# TakpadV6_1.net
KiCad netlist of a schematic drawn in EAGLE
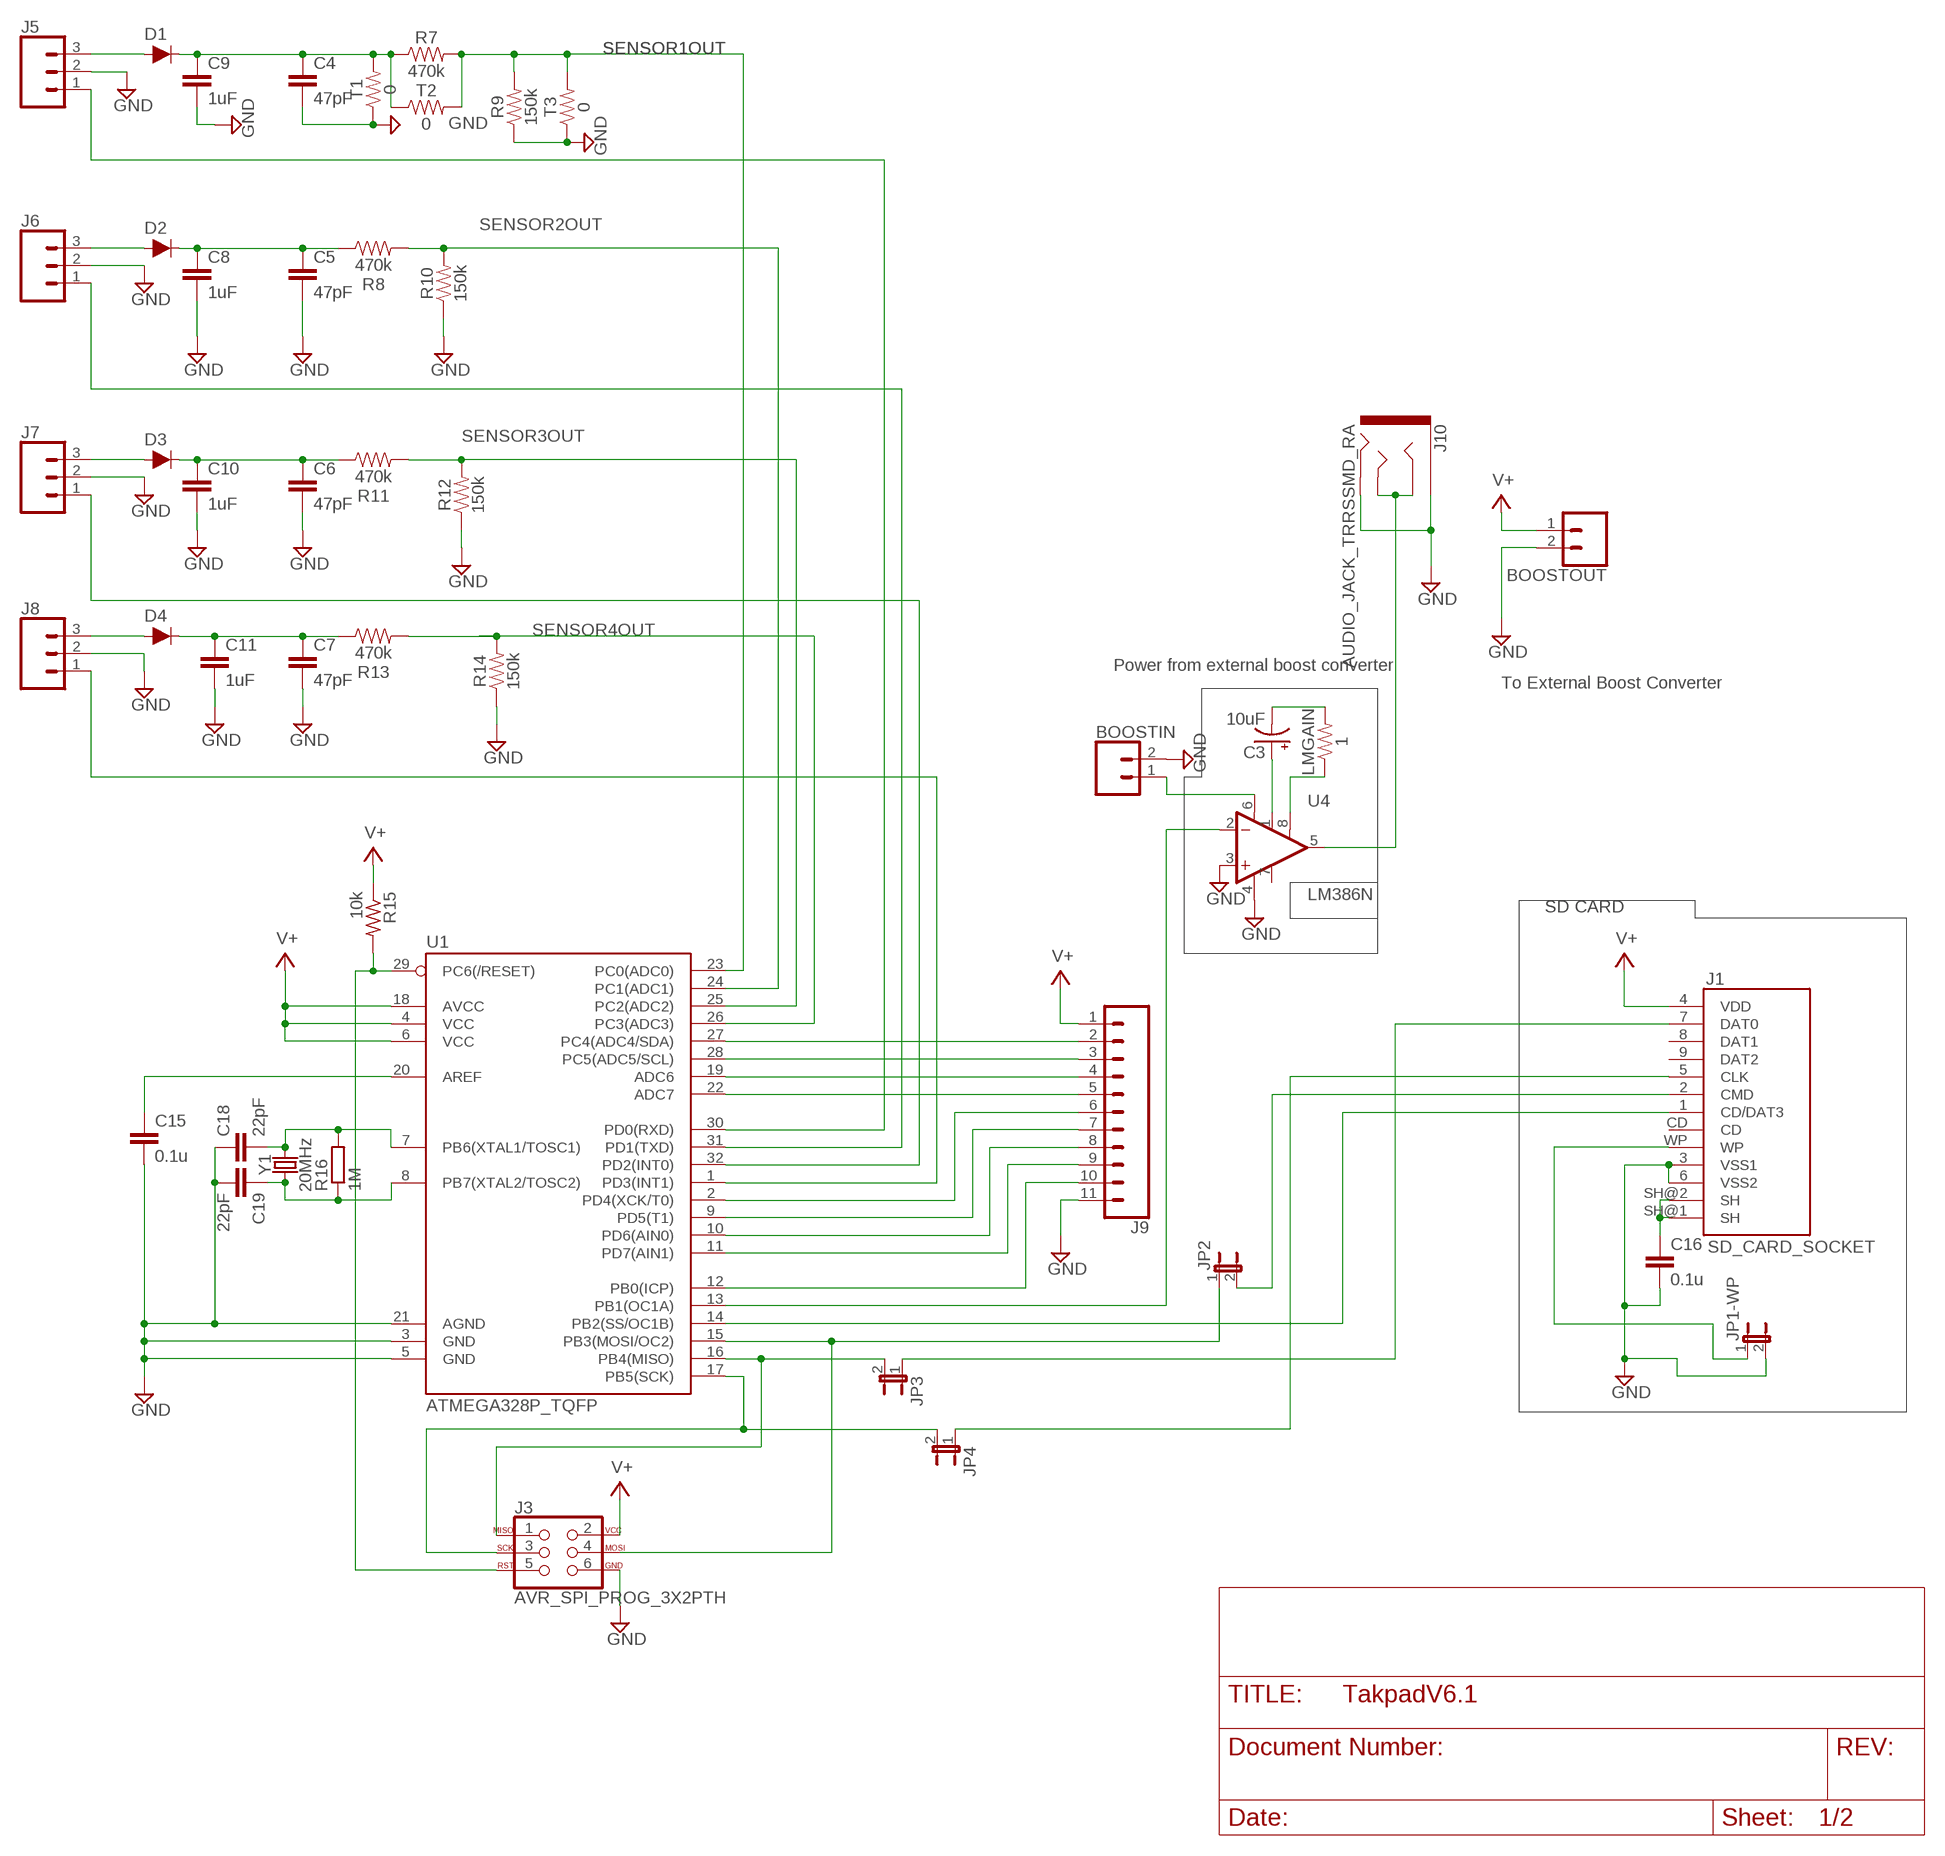
[diagram p0: schematic, sheet 1]
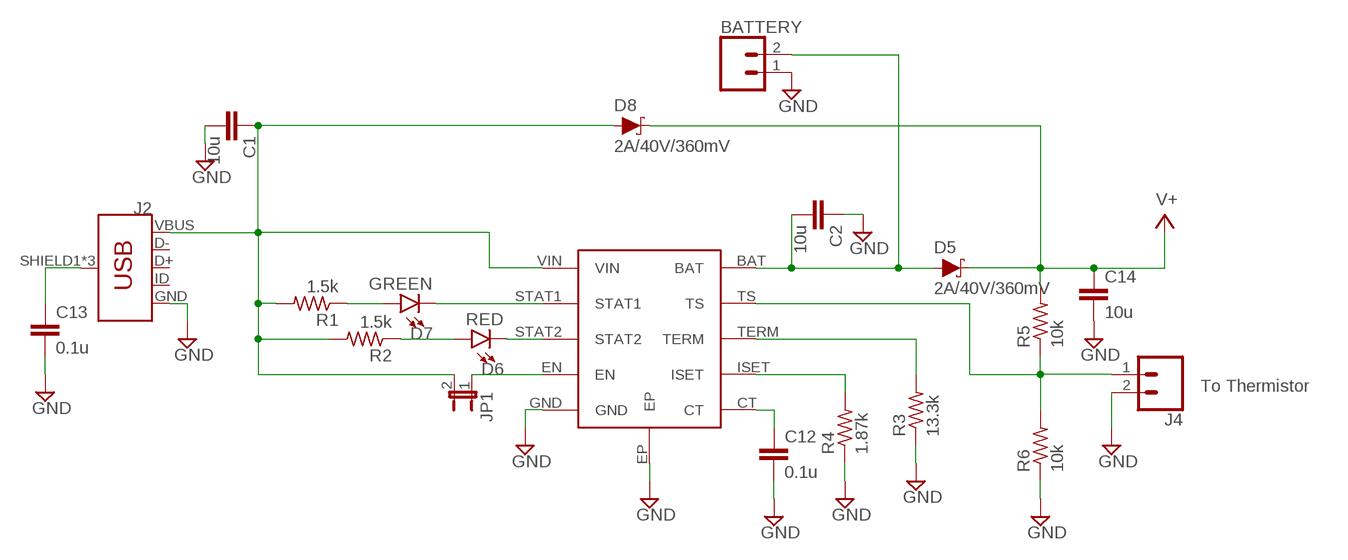
[diagram p1: schematic, sheet 2]

(export (version "E")
  (design (tool "Eeschema 10.0.6"))
  (components
    (comp (ref "BOOSTIN")
      (value "CONN_02")
      (footprint "eagle-import:1X02")
      (libsource (lib "eagle-import") (part "CONN_02"))
    )
    (comp (ref "BOOSTOUT")
      (value "CONN_02")
      (footprint "eagle-import:1X02")
      (libsource (lib "eagle-import") (part "CONN_02"))
    )
    (comp (ref "C3")
      (value "10uF")
      (footprint "eagle-import:CPOL-RADIAL-2.5MM-5MM-KIT")
      (libsource (lib "eagle-import") (part "10UF-POLAR-RADIAL-2.5MM-KIT-25V-20%"))
    )
    (comp (ref "C4")
      (value "47pF")
      (footprint "eagle-import:0603")
      (libsource (lib "eagle-import") (part "47PF-0603-50V-5%"))
    )
    (comp (ref "C5")
      (value "47pF")
      (footprint "eagle-import:0603")
      (libsource (lib "eagle-import") (part "47PF-0603-50V-5%"))
    )
    (comp (ref "C6")
      (value "47pF")
      (footprint "eagle-import:0603")
      (libsource (lib "eagle-import") (part "47PF-0603-50V-5%"))
    )
    (comp (ref "C7")
      (value "47pF")
      (footprint "eagle-import:0603")
      (libsource (lib "eagle-import") (part "47PF-0603-50V-5%"))
    )
    (comp (ref "C8")
      (value "1uF")
      (footprint "eagle-import:0603")
      (libsource (lib "eagle-import") (part "47PF-0603-50V-5%"))
    )
    (comp (ref "C9")
      (value "1uF")
      (footprint "eagle-import:0603")
      (libsource (lib "eagle-import") (part "47PF-0603-50V-5%"))
    )
    (comp (ref "C10")
      (value "1uF")
      (footprint "eagle-import:0603")
      (libsource (lib "eagle-import") (part "47PF-0603-50V-5%"))
    )
    (comp (ref "C11")
      (value "1uF")
      (footprint "eagle-import:0603")
      (libsource (lib "eagle-import") (part "47PF-0603-50V-5%"))
    )
    (comp (ref "C15")
      (value "0.1u")
      (footprint "eagle-import:C0402")
      (libsource (lib "eagle-import") (part "C-EUC0402"))
    )
    (comp (ref "C16")
      (value "0.1u")
      (footprint "eagle-import:C0402")
      (libsource (lib "eagle-import") (part "C-EUC0402"))
    )
    (comp (ref "C18")
      (value "22pF")
      (footprint "eagle-import:C0402")
      (libsource (lib "eagle-import") (part "resistor_348_C-EUC0402"))
    )
    (comp (ref "C19")
      (value "22pF")
      (footprint "eagle-import:C0402")
      (libsource (lib "eagle-import") (part "resistor_348_C-EUC0402"))
    )
    (comp (ref "D1")
      (value "200mA/100V/1V")
      (footprint "eagle-import:DIODE-1N4148")
      (libsource (lib "eagle-import") (part "DIODE-1N4148"))
    )
    (comp (ref "D2")
      (value "200mA/100V/1V")
      (footprint "eagle-import:DIODE-1N4148")
      (libsource (lib "eagle-import") (part "DIODE-1N4148"))
    )
    (comp (ref "D3")
      (value "200mA/100V/1V")
      (footprint "eagle-import:DIODE-1N4148")
      (libsource (lib "eagle-import") (part "DIODE-1N4148"))
    )
    (comp (ref "D4")
      (value "200mA/100V/1V")
      (footprint "eagle-import:DIODE-1N4148")
      (libsource (lib "eagle-import") (part "DIODE-1N4148"))
    )
    (comp (ref "J1")
      (value "SD_CARD_SOCKET")
      (footprint "eagle-import:SD")
      (libsource (lib "eagle-import") (part "SD_CARD_SOCKET"))
    )
    (comp (ref "J3")
      (value "AVR_SPI_PROG_3X2PTH")
      (footprint "eagle-import:2X3")
      (libsource (lib "eagle-import") (part "AVR_SPI_PROG_3X2PTH"))
    )
    (comp (ref "J5")
      (value "CONN_03")
      (footprint "eagle-import:1X03")
      (libsource (lib "eagle-import") (part "CONN_03"))
    )
    (comp (ref "J6")
      (value "CONN_03")
      (footprint "eagle-import:1X03")
      (libsource (lib "eagle-import") (part "CONN_03"))
    )
    (comp (ref "J7")
      (value "CONN_03")
      (footprint "eagle-import:1X03")
      (libsource (lib "eagle-import") (part "CONN_03"))
    )
    (comp (ref "J8")
      (value "CONN_03")
      (footprint "eagle-import:1X03")
      (libsource (lib "eagle-import") (part "CONN_03"))
    )
    (comp (ref "J9")
      (value "CONN_11")
      (footprint "eagle-import:1X11")
      (libsource (lib "eagle-import") (part "CONN_11"))
    )
    (comp (ref "J10")
      (value "AUDIO_JACK_TRRSSMD_RA")
      (footprint "eagle-import:AUDIO_JACK_3.5MM_TRRS_SMD_RA")
      (libsource (lib "eagle-import") (part "AUDIO_JACK_TRRSSMD_RA"))
    )
    (comp (ref "JP1-WP")
      (value "JUMPER-2PTH")
      (footprint "eagle-import:1X02")
      (libsource (lib "eagle-import") (part "JUMPER-2PTH"))
    )
    (comp (ref "JP2")
      (value "JUMPER-2PTH")
      (footprint "eagle-import:1X02")
      (libsource (lib "eagle-import") (part "JUMPER-2PTH"))
    )
    (comp (ref "JP3")
      (value "JUMPER-2PTH")
      (footprint "eagle-import:1X02")
      (libsource (lib "eagle-import") (part "JUMPER-2PTH"))
    )
    (comp (ref "JP4")
      (value "JUMPER-2PTH")
      (footprint "eagle-import:1X02")
      (libsource (lib "eagle-import") (part "JUMPER-2PTH"))
    )
    (comp (ref "LMGAIN")
      (value "1")
      (footprint "eagle-import:0603")
      (libsource (lib "eagle-import") (part "1OHM-0603-1/10W-1%"))
    )
    (comp (ref "R7")
      (value "470k")
      (footprint "eagle-import:AXIAL-0.3")
      (libsource (lib "eagle-import") (part "1KOHM-HORIZ-1/4W-1%"))
    )
    (comp (ref "R8")
      (value "470k")
      (footprint "eagle-import:AXIAL-0.3")
      (libsource (lib "eagle-import") (part "1KOHM-HORIZ-1/4W-1%"))
    )
    (comp (ref "R9")
      (value "150k")
      (footprint "eagle-import:AXIAL-0.3")
      (libsource (lib "eagle-import") (part "1KOHM-HORIZ-1/4W-1%"))
    )
    (comp (ref "R10")
      (value "150k")
      (footprint "eagle-import:AXIAL-0.3")
      (libsource (lib "eagle-import") (part "1KOHM-HORIZ-1/4W-1%"))
    )
    (comp (ref "R11")
      (value "470k")
      (footprint "eagle-import:AXIAL-0.3")
      (libsource (lib "eagle-import") (part "1KOHM-HORIZ-1/4W-1%"))
    )
    (comp (ref "R12")
      (value "150k")
      (footprint "eagle-import:AXIAL-0.3")
      (libsource (lib "eagle-import") (part "1KOHM-HORIZ-1/4W-1%"))
    )
    (comp (ref "R13")
      (value "470k")
      (footprint "eagle-import:AXIAL-0.3")
      (libsource (lib "eagle-import") (part "1KOHM-HORIZ-1/4W-1%"))
    )
    (comp (ref "R14")
      (value "150k")
      (footprint "eagle-import:AXIAL-0.3")
      (libsource (lib "eagle-import") (part "1KOHM-HORIZ-1/4W-1%"))
    )
    (comp (ref "R15")
      (value "10k")
      (footprint "eagle-import:M1206")
      (libsource (lib "eagle-import") (part "R-US_M1206"))
    )
    (comp (ref "R16")
      (value "1M")
      (footprint "eagle-import:R0402")
      (libsource (lib "eagle-import") (part "R-EU_R0402"))
    )
    (comp (ref "T1")
      (value "0")
      (footprint "eagle-import:AXIAL-0.3")
      (libsource (lib "eagle-import") (part "1KOHM-HORIZ-1/4W-1%"))
    )
    (comp (ref "T2")
      (value "0")
      (footprint "eagle-import:AXIAL-0.3")
      (libsource (lib "eagle-import") (part "1KOHM-HORIZ-1/4W-1%"))
    )
    (comp (ref "T3")
      (value "0")
      (footprint "eagle-import:AXIAL-0.3")
      (libsource (lib "eagle-import") (part "1KOHM-HORIZ-1/4W-1%"))
    )
    (comp (ref "U1")
      (value "ATMEGA328P_TQFP")
      (footprint "eagle-import:TQFP32-08")
      (libsource (lib "eagle-import") (part "ATMEGA328P_TQFP"))
    )
    (comp (ref "U4")
      (value "LM386N")
      (footprint "eagle-import:DIP08")
      (libsource (lib "eagle-import") (part "LM386"))
    )
    (comp (ref "Y1")
      (value "20MHz")
      (footprint "eagle-import:HC49US")
      (libsource (lib "eagle-import") (part "CRYSTAL-16MHZPTH-HC49US"))
    )
    (comp (ref "BATTERY")
      (value "CONN_02")
      (footprint "eagle-import:1X02")
      (libsource (lib "eagle-import") (part "CONN_02"))
    )
    (comp (ref "C1")
      (value "10u")
      (footprint "eagle-import:C0402")
      (libsource (lib "eagle-import") (part "C-EUC0402"))
    )
    (comp (ref "C2")
      (value "10u")
      (footprint "eagle-import:C0402")
      (libsource (lib "eagle-import") (part "C-EUC0402"))
    )
    (comp (ref "C12")
      (value "0.1u")
      (footprint "eagle-import:C0402")
      (libsource (lib "eagle-import") (part "C-EUC0402"))
    )
    (comp (ref "C13")
      (value "0.1u")
      (footprint "eagle-import:C0402")
      (libsource (lib "eagle-import") (part "C-EUC0402"))
    )
    (comp (ref "C14")
      (value "10u")
      (footprint "eagle-import:C0402")
      (libsource (lib "eagle-import") (part "C-EUC0402"))
    )
    (comp (ref "D5")
      (value "2A/40V/360mV")
      (footprint "eagle-import:SMA-DIODE")
      (libsource (lib "eagle-import") (part "DIODE-SCHOTTKY-B340A"))
    )
    (comp (ref "D6")
      (value "RED")
      (footprint "eagle-import:LED-1206")
      (libsource (lib "eagle-import") (part "LED-RED1206"))
    )
    (comp (ref "D7")
      (value "GREEN")
      (footprint "eagle-import:LED-1206")
      (libsource (lib "eagle-import") (part "LED-GREEN1206"))
    )
    (comp (ref "D8")
      (value "2A/40V/360mV")
      (footprint "eagle-import:SMA-DIODE")
      (libsource (lib "eagle-import") (part "DIODE-SCHOTTKY-B340A"))
    )
    (comp (ref "J2")
      (value "USB_MICRO-BREDUCED_PASTE")
      (footprint "eagle-import:USB-B-MICRO-SMD_RED_PASTE")
      (libsource (lib "eagle-import") (part "USB_MICRO-BREDUCED_PASTE"))
    )
    (comp (ref "J4")
      (value "CONN_02")
      (footprint "eagle-import:1X02")
      (libsource (lib "eagle-import") (part "CONN_02"))
    )
    (comp (ref "JP1")
      (value "JUMPER-2PTH")
      (footprint "eagle-import:1X02")
      (libsource (lib "eagle-import") (part "JUMPER-2PTH"))
    )
    (comp (ref "R1")
      (value "1.5k")
      (footprint "eagle-import:M1206")
      (libsource (lib "eagle-import") (part "R-US_M1206"))
    )
    (comp (ref "R2")
      (value "1.5k")
      (footprint "eagle-import:M1206")
      (libsource (lib "eagle-import") (part "R-US_M1206"))
    )
    (comp (ref "R3")
      (value "13.3k")
      (footprint "eagle-import:M1206")
      (libsource (lib "eagle-import") (part "R-US_M1206"))
    )
    (comp (ref "R4")
      (value "1.87k")
      (footprint "eagle-import:M1206")
      (libsource (lib "eagle-import") (part "R-US_M1206"))
    )
    (comp (ref "R5")
      (value "10k")
      (footprint "eagle-import:M1206")
      (libsource (lib "eagle-import") (part "R-US_M1206"))
    )
    (comp (ref "R6")
      (value "10k")
      (footprint "eagle-import:M1206")
      (libsource (lib "eagle-import") (part "R-US_M1206"))
    )
    (comp (ref "U$1")
      (value "AAT3693")
      (footprint "eagle-import:IDH-AA-T1")
      (libsource (lib "eagle-import") (part "AAT3693"))
    )
  )
  (nets
    (net (code "1") (name "GND") (class "Default")
      (node (ref "BATTERY") (pin "1") (pinfunction "1_1") (pintype "passive"))
      (node (ref "BOOSTIN") (pin "2") (pinfunction "2_2") (pintype "passive"))
      (node (ref "BOOSTOUT") (pin "2") (pinfunction "2_2") (pintype "passive"))
      (node (ref "C1") (pin "2") (pinfunction "2_2") (pintype "passive"))
      (node (ref "C10") (pin "2") (pinfunction "2_2") (pintype "passive"))
      (node (ref "C11") (pin "2") (pinfunction "2_2") (pintype "passive"))
      (node (ref "C12") (pin "2") (pinfunction "2_2") (pintype "passive"))
      (node (ref "C13") (pin "2") (pinfunction "2_2") (pintype "passive"))
      (node (ref "C14") (pin "2") (pinfunction "2_2") (pintype "passive"))
      (node (ref "C15") (pin "2") (pinfunction "2_2") (pintype "passive"))
      (node (ref "C16") (pin "2") (pinfunction "2_2") (pintype "passive"))
      (node (ref "C18") (pin "1") (pinfunction "1_1") (pintype "passive"))
      (node (ref "C19") (pin "2") (pinfunction "2_2") (pintype "passive"))
      (node (ref "C2") (pin "1") (pinfunction "1_1") (pintype "passive"))
      (node (ref "C4") (pin "2") (pinfunction "2_2") (pintype "passive"))
      (node (ref "C5") (pin "2") (pinfunction "2_2") (pintype "passive"))
      (node (ref "C6") (pin "2") (pinfunction "2_2") (pintype "passive"))
      (node (ref "C7") (pin "2") (pinfunction "2_2") (pintype "passive"))
      (node (ref "C8") (pin "2") (pinfunction "2_2") (pintype "passive"))
      (node (ref "C9") (pin "2") (pinfunction "2_2") (pintype "passive"))
      (node (ref "J1") (pin "3") (pinfunction "VSS1_3") (pintype "power_in"))
      (node (ref "J1") (pin "6") (pinfunction "VSS2_6") (pintype "power_in"))
      (node (ref "J10") (pin "EARTH") (pinfunction "EARTH_EARTH") (pintype "bidirectional"))
      (node (ref "J10") (pin "RING2") (pinfunction "RING2_RING2") (pintype "bidirectional"))
      (node (ref "J2") (pin "GND") (pinfunction "GND_GND") (pintype "power_in"))
      (node (ref "J3") (pin "6") (pinfunction "6_6") (pintype "passive"))
      (node (ref "J4") (pin "2") (pinfunction "2_2") (pintype "passive"))
      (node (ref "J5") (pin "2") (pinfunction "2_2") (pintype "passive"))
      (node (ref "J6") (pin "2") (pinfunction "2_2") (pintype "passive"))
      (node (ref "J7") (pin "2") (pinfunction "2_2") (pintype "passive"))
      (node (ref "J8") (pin "2") (pinfunction "2_2") (pintype "passive"))
      (node (ref "J9") (pin "11") (pinfunction "11_11") (pintype "passive"))
      (node (ref "JP1-WP") (pin "2") (pinfunction "2_2") (pintype "passive"))
      (node (ref "R10") (pin "P$1") (pinfunction "1_P$1") (pintype "passive"))
      (node (ref "R12") (pin "P$1") (pinfunction "1_P$1") (pintype "passive"))
      (node (ref "R14") (pin "P$1") (pinfunction "1_P$1") (pintype "passive"))
      (node (ref "R3") (pin "1") (pinfunction "1_1") (pintype "passive"))
      (node (ref "R4") (pin "1") (pinfunction "1_1") (pintype "passive"))
      (node (ref "R6") (pin "1") (pinfunction "1_1") (pintype "passive"))
      (node (ref "R9") (pin "P$1") (pinfunction "1_P$1") (pintype "passive"))
      (node (ref "T1") (pin "P$1") (pinfunction "1_P$1") (pintype "passive"))
      (node (ref "T3") (pin "P$1") (pinfunction "1_P$1") (pintype "passive"))
      (node (ref "U$1") (pin "EP") (pinfunction "EP_EP") (pintype "bidirectional"))
      (node (ref "U$1") (pin "GND") (pinfunction "GND_GND") (pintype "bidirectional"))
      (node (ref "U1") (pin "21") (pinfunction "AGND_21") (pintype "bidirectional"))
      (node (ref "U1") (pin "3") (pinfunction "GND_3") (pintype "bidirectional"))
      (node (ref "U1") (pin "5") (pinfunction "GND_5") (pintype "bidirectional"))
      (node (ref "U4") (pin "3") (pinfunction "+IN_3") (pintype "input"))
      (node (ref "U4") (pin "4") (pinfunction "V-_4") (pintype "power_in"))
    )
    (net (code "2") (name "Net-(BATTERY-Pad2)") (class "Default")
      (node (ref "BATTERY") (pin "2") (pinfunction "2_2") (pintype "passive"))
      (node (ref "C2") (pin "2") (pinfunction "2_2") (pintype "passive"))
      (node (ref "D5") (pin "A") (pinfunction "A_A") (pintype "passive"))
      (node (ref "U$1") (pin "BAT") (pinfunction "BAT_BAT") (pintype "bidirectional"))
    )
    (net (code "3") (name "Net-(C1-Pad1)") (class "Default")
      (node (ref "C1") (pin "1") (pinfunction "1_1") (pintype "passive"))
      (node (ref "D8") (pin "A") (pinfunction "A_A") (pintype "passive"))
      (node (ref "J2") (pin "VBUS") (pinfunction "VBUS_VBUS") (pintype "power_in"))
      (node (ref "JP1") (pin "2") (pinfunction "2_2") (pintype "passive"))
      (node (ref "R1") (pin "2") (pinfunction "2_2") (pintype "passive"))
      (node (ref "R2") (pin "2") (pinfunction "2_2") (pintype "passive"))
      (node (ref "U$1") (pin "VIN") (pinfunction "VIN_VIN") (pintype "bidirectional"))
    )
    (net (code "4") (name "Net-(C3-+)") (class "Default")
      (node (ref "C3") (pin "1") (pinfunction "+_1") (pintype "passive"))
      (node (ref "U4") (pin "1") (pinfunction "GAIN_1") (pintype "bidirectional"))
    )
    (net (code "5") (name "Net-(C3--)") (class "Default")
      (node (ref "C3") (pin "2") (pinfunction "-_2") (pintype "passive"))
      (node (ref "LMGAIN") (pin "2") (pinfunction "2_2") (pintype "passive"))
    )
    (net (code "6") (name "Net-(C12-Pad1)") (class "Default")
      (node (ref "C12") (pin "1") (pinfunction "1_1") (pintype "passive"))
      (node (ref "U$1") (pin "CT") (pinfunction "CT_CT") (pintype "bidirectional"))
    )
    (net (code "7") (name "Net-(C13-Pad1)") (class "Default")
      (node (ref "C13") (pin "1") (pinfunction "1_1") (pintype "passive"))
      (node (ref "J2") (pin "SHIELD1") (pinfunction "SHIELD_SHIELD1") (pintype "bidirectional"))
      (node (ref "J2") (pin "SHIELD2") (pinfunction "SHIELD_SHIELD2") (pintype "bidirectional"))
      (node (ref "J2") (pin "SHIELD3") (pinfunction "SHIELD_SHIELD3") (pintype "bidirectional"))
    )
    (net (code "8") (name "Net-(C16-Pad1)") (class "Default")
      (node (ref "C16") (pin "1") (pinfunction "1_1") (pintype "passive"))
      (node (ref "J1") (pin "SH@1") (pinfunction "SH_SH@1") (pintype "bidirectional"))
      (node (ref "J1") (pin "SH@2") (pinfunction "SH_SH@2") (pintype "bidirectional"))
    )
    (net (code "9") (name "Net-(D1-PadA)") (class "Default")
      (node (ref "D1") (pin "A") (pinfunction "A_A") (pintype "passive"))
      (node (ref "J5") (pin "3") (pinfunction "3_3") (pintype "passive"))
    )
    (net (code "10") (name "Net-(D2-PadA)") (class "Default")
      (node (ref "D2") (pin "A") (pinfunction "A_A") (pintype "passive"))
      (node (ref "J6") (pin "3") (pinfunction "3_3") (pintype "passive"))
    )
    (net (code "11") (name "Net-(D3-PadA)") (class "Default")
      (node (ref "D3") (pin "A") (pinfunction "A_A") (pintype "passive"))
      (node (ref "J7") (pin "3") (pinfunction "3_3") (pintype "passive"))
    )
    (net (code "12") (name "Net-(D4-PadA)") (class "Default")
      (node (ref "D4") (pin "A") (pinfunction "A_A") (pintype "passive"))
      (node (ref "J8") (pin "3") (pinfunction "3_3") (pintype "passive"))
    )
    (net (code "13") (name "Net-(D6-PadA)") (class "Default")
      (node (ref "D6") (pin "A") (pinfunction "A_A") (pintype "passive"))
      (node (ref "R2") (pin "1") (pinfunction "1_1") (pintype "passive"))
    )
    (net (code "14") (name "Net-(D6-PadC)") (class "Default")
      (node (ref "D6") (pin "C") (pinfunction "C_C") (pintype "passive"))
      (node (ref "U$1") (pin "STAT2") (pinfunction "STAT2_STAT2") (pintype "bidirectional"))
    )
    (net (code "15") (name "Net-(D7-PadA)") (class "Default")
      (node (ref "D7") (pin "A") (pinfunction "A_A") (pintype "passive"))
      (node (ref "R1") (pin "1") (pinfunction "1_1") (pintype "passive"))
    )
    (net (code "16") (name "Net-(D7-PadC)") (class "Default")
      (node (ref "D7") (pin "C") (pinfunction "C_C") (pintype "passive"))
      (node (ref "U$1") (pin "STAT1") (pinfunction "STAT1_STAT1") (pintype "bidirectional"))
    )
    (net (code "17") (name "Net-(J1-CD{slash}DAT3)") (class "Default")
      (node (ref "J1") (pin "1") (pinfunction "CD/DAT3_1") (pintype "bidirectional"))
      (node (ref "U1") (pin "14") (pinfunction "PB2(SS/OC1B)_14") (pintype "bidirectional"))
    )
    (net (code "18") (name "Net-(J1-CLK)") (class "Default")
      (node (ref "J1") (pin "5") (pinfunction "CLK_5") (pintype "bidirectional"))
      (node (ref "JP4") (pin "1") (pinfunction "1_1") (pintype "passive"))
    )
    (net (code "19") (name "Net-(J1-CMD)") (class "Default")
      (node (ref "J1") (pin "2") (pinfunction "CMD_2") (pintype "bidirectional"))
      (node (ref "JP2") (pin "2") (pinfunction "2_2") (pintype "passive"))
    )
    (net (code "20") (name "Net-(J1-DAT0)") (class "Default")
      (node (ref "J1") (pin "7") (pinfunction "DAT0_7") (pintype "bidirectional"))
      (node (ref "JP3") (pin "1") (pinfunction "1_1") (pintype "passive"))
    )
    (net (code "21") (name "Net-(J1-PadWP)") (class "Default")
      (node (ref "J1") (pin "WP") (pinfunction "WP_WP") (pintype "bidirectional"))
      (node (ref "JP1-WP") (pin "1") (pinfunction "1_1") (pintype "passive"))
    )
    (net (code "22") (name "Net-(J4-Pad1)") (class "Default")
      (node (ref "J4") (pin "1") (pinfunction "1_1") (pintype "passive"))
      (node (ref "R5") (pin "1") (pinfunction "1_1") (pintype "passive"))
      (node (ref "R6") (pin "2") (pinfunction "2_2") (pintype "passive"))
      (node (ref "U$1") (pin "TS") (pinfunction "TS_TS") (pintype "bidirectional"))
    )
    (net (code "23") (name "Net-(JP1-Pad1)") (class "Default")
      (node (ref "JP1") (pin "1") (pinfunction "1_1") (pintype "passive"))
      (node (ref "U$1") (pin "EN") (pinfunction "EN_EN") (pintype "bidirectional"))
    )
    (net (code "24") (name "Net-(LMGAIN-Pad1)") (class "Default")
      (node (ref "LMGAIN") (pin "1") (pinfunction "1_1") (pintype "passive"))
      (node (ref "U4") (pin "8") (pinfunction "GAIN_8") (pintype "bidirectional"))
    )
    (net (code "25") (name "Net-(R3-Pad2)") (class "Default")
      (node (ref "R3") (pin "2") (pinfunction "2_2") (pintype "passive"))
      (node (ref "U$1") (pin "TERM") (pinfunction "TERM_TERM") (pintype "bidirectional"))
    )
    (net (code "26") (name "Net-(R4-Pad2)") (class "Default")
      (node (ref "R4") (pin "2") (pinfunction "2_2") (pintype "passive"))
      (node (ref "U$1") (pin "ISET") (pinfunction "ISET_ISET") (pintype "bidirectional"))
    )
    (net (code "27") (name "Net-(R7-1)") (class "Default")
      (node (ref "C4") (pin "1") (pinfunction "1_1") (pintype "passive"))
      (node (ref "C9") (pin "1") (pinfunction "1_1") (pintype "passive"))
      (node (ref "D1") (pin "C") (pinfunction "C_C") (pintype "passive"))
      (node (ref "R7") (pin "P$1") (pinfunction "1_P$1") (pintype "passive"))
      (node (ref "T1") (pin "P$2") (pinfunction "2_P$2") (pintype "passive"))
      (node (ref "T2") (pin "P$1") (pinfunction "1_P$1") (pintype "passive"))
    )
    (net (code "28") (name "Net-(R8-1)") (class "Default")
      (node (ref "C5") (pin "1") (pinfunction "1_1") (pintype "passive"))
      (node (ref "C8") (pin "1") (pinfunction "1_1") (pintype "passive"))
      (node (ref "D2") (pin "C") (pinfunction "C_C") (pintype "passive"))
      (node (ref "R8") (pin "P$1") (pinfunction "1_P$1") (pintype "passive"))
    )
    (net (code "29") (name "Net-(R11-1)") (class "Default")
      (node (ref "C10") (pin "1") (pinfunction "1_1") (pintype "passive"))
      (node (ref "C6") (pin "1") (pinfunction "1_1") (pintype "passive"))
      (node (ref "D3") (pin "C") (pinfunction "C_C") (pintype "passive"))
      (node (ref "R11") (pin "P$1") (pinfunction "1_P$1") (pintype "passive"))
    )
    (net (code "30") (name "Net-(R13-1)") (class "Default")
      (node (ref "C11") (pin "1") (pinfunction "1_1") (pintype "passive"))
      (node (ref "C7") (pin "1") (pinfunction "1_1") (pintype "passive"))
      (node (ref "D4") (pin "C") (pinfunction "C_C") (pintype "passive"))
      (node (ref "R13") (pin "P$1") (pinfunction "1_P$1") (pintype "passive"))
    )
    (net (code "31") (name "Net-(U1-ADC6)") (class "Default")
      (node (ref "J9") (pin "4") (pinfunction "4_4") (pintype "passive"))
      (node (ref "U1") (pin "19") (pinfunction "ADC6_19") (pintype "bidirectional"))
    )
    (net (code "32") (name "Net-(U1-ADC7)") (class "Default")
      (node (ref "J9") (pin "5") (pinfunction "5_5") (pintype "passive"))
      (node (ref "U1") (pin "22") (pinfunction "ADC7_22") (pintype "bidirectional"))
    )
    (net (code "33") (name "Net-(U1-AREF)") (class "Default")
      (node (ref "C15") (pin "1") (pinfunction "1_1") (pintype "passive"))
      (node (ref "U1") (pin "20") (pinfunction "AREF_20") (pintype "bidirectional"))
    )
    (net (code "34") (name "Net-(U1-PB0(ICP))") (class "Default")
      (node (ref "J9") (pin "10") (pinfunction "10_10") (pintype "passive"))
      (node (ref "U1") (pin "12") (pinfunction "PB0(ICP)_12") (pintype "bidirectional"))
    )
    (net (code "35") (name "Net-(U1-PB1(OC1A))") (class "Default")
      (node (ref "U1") (pin "13") (pinfunction "PB1(OC1A)_13") (pintype "bidirectional"))
      (node (ref "U4") (pin "2") (pinfunction "-IN_2") (pintype "input"))
    )
    (net (code "36") (name "Net-(U1-PB3(MOSI{slash}OC2))") (class "Default")
      (node (ref "J3") (pin "4") (pinfunction "4_4") (pintype "passive"))
      (node (ref "JP2") (pin "1") (pinfunction "1_1") (pintype "passive"))
      (node (ref "U1") (pin "15") (pinfunction "PB3(MOSI/OC2)_15") (pintype "bidirectional"))
    )
    (net (code "37") (name "Net-(U1-PB4(MISO))") (class "Default")
      (node (ref "J3") (pin "1") (pinfunction "1_1") (pintype "passive"))
      (node (ref "JP3") (pin "2") (pinfunction "2_2") (pintype "passive"))
      (node (ref "U1") (pin "16") (pinfunction "PB4(MISO)_16") (pintype "bidirectional"))
    )
    (net (code "38") (name "Net-(U1-PB5(SCK))") (class "Default")
      (node (ref "J3") (pin "3") (pinfunction "3_3") (pintype "passive"))
      (node (ref "JP4") (pin "2") (pinfunction "2_2") (pintype "passive"))
      (node (ref "U1") (pin "17") (pinfunction "PB5(SCK)_17") (pintype "bidirectional"))
    )
    (net (code "39") (name "Net-(U1-PB6(XTAL1{slash}TOSC1))") (class "Default")
      (node (ref "C18") (pin "2") (pinfunction "2_2") (pintype "passive"))
      (node (ref "R16") (pin "2") (pinfunction "2_2") (pintype "passive"))
      (node (ref "U1") (pin "7") (pinfunction "PB6(XTAL1/TOSC1)_7") (pintype "bidirectional"))
      (node (ref "Y1") (pin "2") (pinfunction "2_2") (pintype "passive"))
    )
    (net (code "40") (name "Net-(U1-PB7(XTAL2{slash}TOSC2))") (class "Default")
      (node (ref "C19") (pin "1") (pinfunction "1_1") (pintype "passive"))
      (node (ref "R16") (pin "1") (pinfunction "1_1") (pintype "passive"))
      (node (ref "U1") (pin "8") (pinfunction "PB7(XTAL2/TOSC2)_8") (pintype "bidirectional"))
      (node (ref "Y1") (pin "1") (pinfunction "1_1") (pintype "passive"))
    )
    (net (code "41") (name "Net-(U1-PC4(ADC4{slash}SDA))") (class "Default")
      (node (ref "J9") (pin "2") (pinfunction "2_2") (pintype "passive"))
      (node (ref "U1") (pin "27") (pinfunction "PC4(ADC4/SDA)_27") (pintype "bidirectional"))
    )
    (net (code "42") (name "Net-(U1-PC5(ADC5{slash}SCL))") (class "Default")
      (node (ref "J9") (pin "3") (pinfunction "3_3") (pintype "passive"))
      (node (ref "U1") (pin "28") (pinfunction "PC5(ADC5/SCL)_28") (pintype "bidirectional"))
    )
    (net (code "43") (name "Net-(U1-PC6({slash}RESET))") (class "Default")
      (node (ref "J3") (pin "5") (pinfunction "5_5") (pintype "passive"))
      (node (ref "R15") (pin "2") (pinfunction "2_2") (pintype "passive"))
      (node (ref "U1") (pin "29") (pinfunction "PC6(/RESET)_29") (pintype "bidirectional"))
    )
    (net (code "44") (name "Net-(U1-PD0(RXD))") (class "Default")
      (node (ref "J5") (pin "1") (pinfunction "1_1") (pintype "passive"))
      (node (ref "U1") (pin "30") (pinfunction "PD0(RXD)_30") (pintype "bidirectional"))
    )
    (net (code "45") (name "Net-(U1-PD1(TXD))") (class "Default")
      (node (ref "J6") (pin "1") (pinfunction "1_1") (pintype "passive"))
      (node (ref "U1") (pin "31") (pinfunction "PD1(TXD)_31") (pintype "bidirectional"))
    )
    (net (code "46") (name "Net-(U1-PD2(INT0))") (class "Default")
      (node (ref "J7") (pin "1") (pinfunction "1_1") (pintype "passive"))
      (node (ref "U1") (pin "32") (pinfunction "PD2(INT0)_32") (pintype "bidirectional"))
    )
    (net (code "47") (name "Net-(U1-PD3(INT1))") (class "Default")
      (node (ref "J8") (pin "1") (pinfunction "1_1") (pintype "passive"))
      (node (ref "U1") (pin "1") (pinfunction "PD3(INT1)_1") (pintype "bidirectional"))
    )
    (net (code "48") (name "Net-(U1-PD4(XCK{slash}T0))") (class "Default")
      (node (ref "J9") (pin "6") (pinfunction "6_6") (pintype "passive"))
      (node (ref "U1") (pin "2") (pinfunction "PD4(XCK/T0)_2") (pintype "bidirectional"))
    )
    (net (code "49") (name "Net-(U1-PD5(T1))") (class "Default")
      (node (ref "J9") (pin "7") (pinfunction "7_7") (pintype "passive"))
      (node (ref "U1") (pin "9") (pinfunction "PD5(T1)_9") (pintype "bidirectional"))
    )
    (net (code "50") (name "Net-(U1-PD6(AIN0))") (class "Default")
      (node (ref "J9") (pin "8") (pinfunction "8_8") (pintype "passive"))
      (node (ref "U1") (pin "10") (pinfunction "PD6(AIN0)_10") (pintype "bidirectional"))
    )
    (net (code "51") (name "Net-(U1-PD7(AIN1))") (class "Default")
      (node (ref "J9") (pin "9") (pinfunction "9_9") (pintype "passive"))
      (node (ref "U1") (pin "11") (pinfunction "PD7(AIN1)_11") (pintype "bidirectional"))
    )
    (net (code "52") (name "Net-(U4-OUT)") (class "Default")
      (node (ref "J10") (pin "RING1") (pinfunction "RING1_RING1") (pintype "bidirectional"))
      (node (ref "J10") (pin "TIP") (pinfunction "TIP_TIP") (pintype "bidirectional"))
      (node (ref "U4") (pin "5") (pinfunction "OUT_5") (pintype "output"))
    )
    (net (code "53") (name "Net-(U4-V+)") (class "Default")
      (node (ref "BOOSTIN") (pin "1") (pinfunction "1_1") (pintype "passive"))
      (node (ref "U4") (pin "6") (pinfunction "V+_6") (pintype "power_in"))
    )
    (net (code "54") (name "SENSOR1OUT") (class "Default")
      (node (ref "R7") (pin "P$2") (pinfunction "2_P$2") (pintype "passive"))
      (node (ref "R9") (pin "P$2") (pinfunction "2_P$2") (pintype "passive"))
      (node (ref "T2") (pin "P$2") (pinfunction "2_P$2") (pintype "passive"))
      (node (ref "T3") (pin "P$2") (pinfunction "2_P$2") (pintype "passive"))
      (node (ref "U1") (pin "23") (pinfunction "PC0(ADC0)_23") (pintype "bidirectional"))
    )
    (net (code "55") (name "SENSOR2OUT") (class "Default")
      (node (ref "R10") (pin "P$2") (pinfunction "2_P$2") (pintype "passive"))
      (node (ref "R8") (pin "P$2") (pinfunction "2_P$2") (pintype "passive"))
      (node (ref "U1") (pin "24") (pinfunction "PC1(ADC1)_24") (pintype "bidirectional"))
    )
    (net (code "56") (name "SENSOR3OUT") (class "Default")
      (node (ref "R11") (pin "P$2") (pinfunction "2_P$2") (pintype "passive"))
      (node (ref "R12") (pin "P$2") (pinfunction "2_P$2") (pintype "passive"))
      (node (ref "U1") (pin "25") (pinfunction "PC2(ADC2)_25") (pintype "bidirectional"))
    )
    (net (code "57") (name "SENSOR4OUT") (class "Default")
      (node (ref "R13") (pin "P$2") (pinfunction "2_P$2") (pintype "passive"))
      (node (ref "R14") (pin "P$2") (pinfunction "2_P$2") (pintype "passive"))
      (node (ref "U1") (pin "26") (pinfunction "PC3(ADC3)_26") (pintype "bidirectional"))
    )
    (net (code "58") (name "V+") (class "Default")
      (node (ref "BOOSTOUT") (pin "1") (pinfunction "1_1") (pintype "passive"))
      (node (ref "C14") (pin "1") (pinfunction "1_1") (pintype "passive"))
      (node (ref "D5") (pin "C") (pinfunction "C_C") (pintype "passive"))
      (node (ref "D8") (pin "C") (pinfunction "C_C") (pintype "passive"))
      (node (ref "J1") (pin "4") (pinfunction "VDD_4") (pintype "power_in"))
      (node (ref "J3") (pin "2") (pinfunction "2_2") (pintype "passive"))
      (node (ref "J9") (pin "1") (pinfunction "1_1") (pintype "passive"))
      (node (ref "R15") (pin "1") (pinfunction "1_1") (pintype "passive"))
      (node (ref "R5") (pin "2") (pinfunction "2_2") (pintype "passive"))
      (node (ref "U1") (pin "18") (pinfunction "AVCC_18") (pintype "bidirectional"))
      (node (ref "U1") (pin "4") (pinfunction "VCC_4") (pintype "bidirectional"))
      (node (ref "U1") (pin "6") (pinfunction "VCC_6") (pintype "bidirectional"))
    )
    (net (code "59") (name "unconnected-(J1-DAT1-Pad8)") (class "Default")
      (node (ref "J1") (pin "8") (pinfunction "DAT1_8") (pintype "bidirectional"))
    )
    (net (code "60") (name "unconnected-(J1-DAT2-Pad9)") (class "Default")
      (node (ref "J1") (pin "9") (pinfunction "DAT2_9") (pintype "bidirectional"))
    )
    (net (code "61") (name "unconnected-(J1-PadCD)") (class "Default")
      (node (ref "J1") (pin "CD") (pinfunction "CD_CD") (pintype "bidirectional"))
    )
    (net (code "62") (name "unconnected-(J2-PadD+)") (class "Default")
      (node (ref "J2") (pin "D+") (pinfunction "D+_D+") (pintype "bidirectional"))
    )
    (net (code "63") (name "unconnected-(J2-PadD-)") (class "Default")
      (node (ref "J2") (pin "D-") (pinfunction "D-_D-") (pintype "bidirectional"))
    )
    (net (code "64") (name "unconnected-(J2-PadID)") (class "Default")
      (node (ref "J2") (pin "ID") (pinfunction "ID_ID") (pintype "bidirectional"))
    )
    (net (code "65") (name "unconnected-(U4-BP-Pad7)") (class "Default")
      (node (ref "U4") (pin "7") (pinfunction "BP_7") (pintype "bidirectional"))
    )
  )
)
